# design.net
KiCad netlist of a schematic drawn in Altium Designer
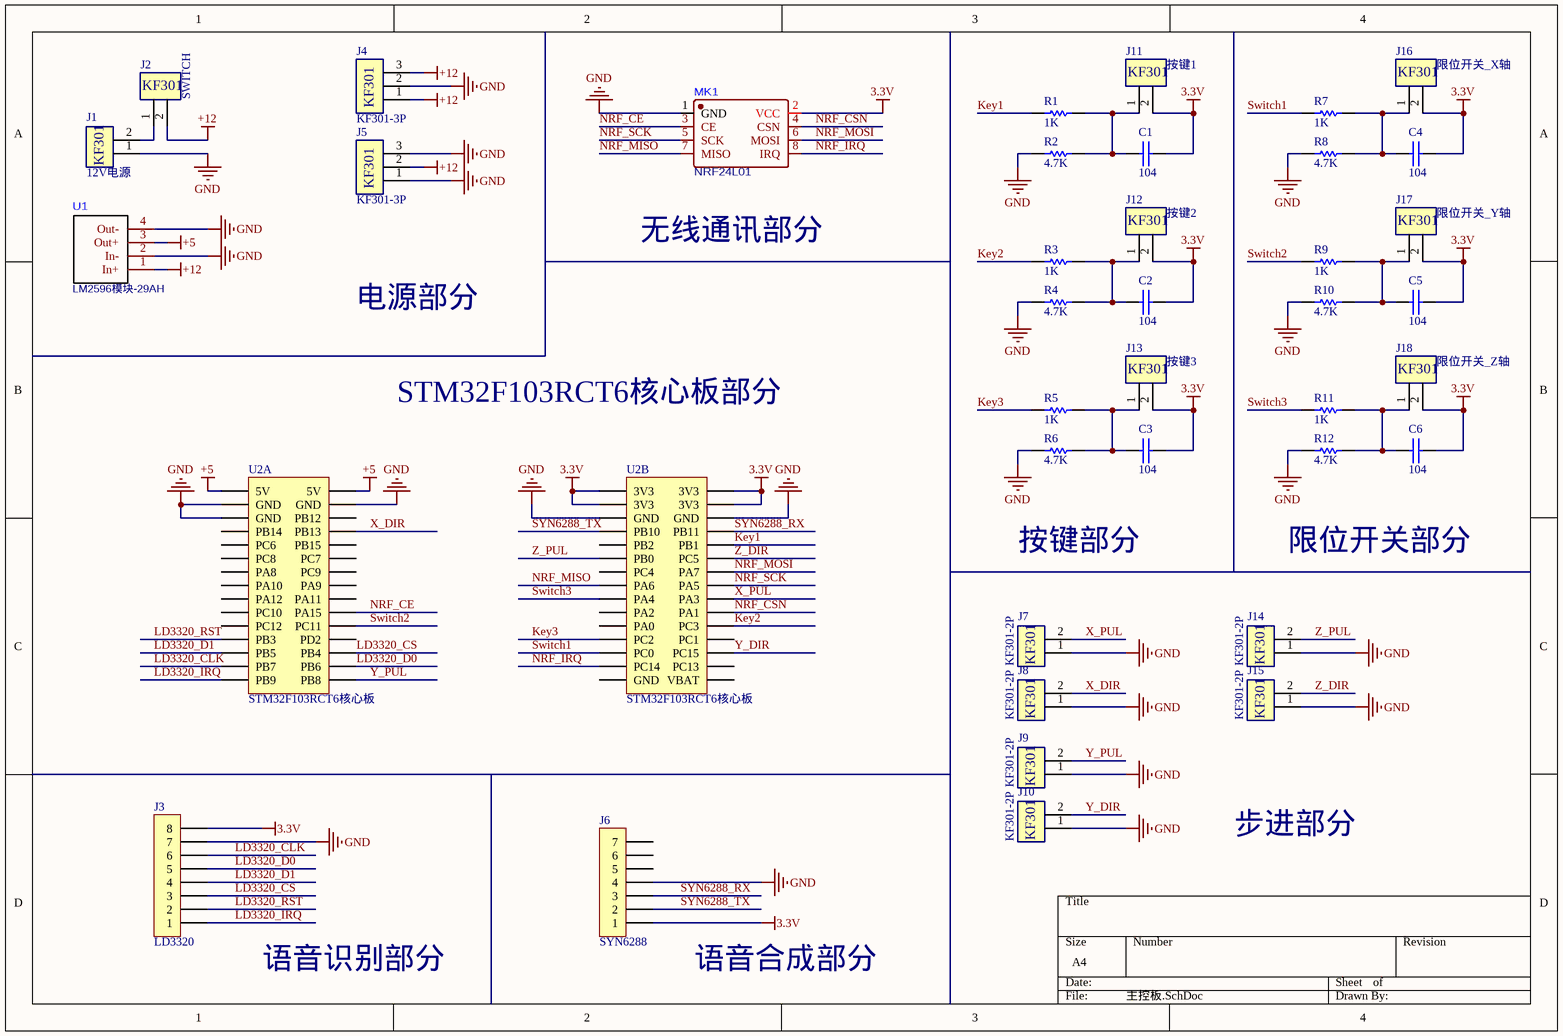
[diagram p0: 主控板.SchDoc]

(export (version "E")
  (design (tool "Eeschema 10.0.6"))
  (components
    (comp (ref "C1")
      (value "104")
      (footprint "0805C")
      (description "无极性电容")
      (libsource (lib "电容") (part "CAP"))
    )
    (comp (ref "C2")
      (value "104")
      (footprint "0805C")
      (description "无极性电容")
      (libsource (lib "电容") (part "CAP"))
    )
    (comp (ref "C3")
      (value "104")
      (footprint "0805C")
      (description "无极性电容")
      (libsource (lib "电容") (part "CAP"))
    )
    (comp (ref "C4")
      (value "104")
      (footprint "0805C")
      (description "无极性电容")
      (libsource (lib "电容") (part "CAP"))
    )
    (comp (ref "C5")
      (value "104")
      (footprint "0805C")
      (description "无极性电容")
      (libsource (lib "电容") (part "CAP"))
    )
    (comp (ref "C6")
      (value "104")
      (footprint "0805C")
      (description "无极性电容")
      (libsource (lib "电容") (part "CAP"))
    )
    (comp (ref "J1") (value "12V电源") (footprint "KF301-5.0-2P") (libsource (lib "") (part "KF301-2P_1")))
    (comp (ref "J2") (value "SWITCH") (footprint "KF301-5.0-2P") (libsource (lib "KF301") (part "KF301-2P")))
    (comp (ref "J3")
      (value "LD3320")
      (footprint "Fe-HDR1X8/2.54-S")
      (libsource (lib "排母") (part "Female HDR1X8"))
    )
    (comp (ref "J4")
      (value "KF301-3P")
      (footprint "KF301-5.0-3P")
      (libsource (lib "KF301") (part "KF301-3P"))
    )
    (comp (ref "J5")
      (value "KF301-3P")
      (footprint "KF301-5.0-3P")
      (libsource (lib "KF301") (part "KF301-3P"))
    )
    (comp (ref "J6")
      (value "SYN6288")
      (footprint "Fe-HDR1X7/2.54-S")
      (libsource (lib "排母") (part "Female HDR1X7"))
    )
    (comp (ref "J7") (value "KF301-2P") (footprint "KF301-5.0-2P") (libsource (lib "") (part "KF301-2P_1")))
    (comp (ref "J8") (value "KF301-2P") (footprint "KF301-5.0-2P") (libsource (lib "") (part "KF301-2P_1")))
    (comp (ref "J9") (value "KF301-2P") (footprint "KF301-5.0-2P") (libsource (lib "") (part "KF301-2P_1")))
    (comp (ref "J10") (value "KF301-2P") (footprint "KF301-5.0-2P") (libsource (lib "") (part "KF301-2P_1")))
    (comp (ref "J11") (value "按键1") (footprint "KF301-5.0-2P") (libsource (lib "KF301") (part "KF301-2P")))
    (comp (ref "J12") (value "按键2") (footprint "KF301-5.0-2P") (libsource (lib "KF301") (part "KF301-2P")))
    (comp (ref "J13") (value "按键3") (footprint "KF301-5.0-2P") (libsource (lib "KF301") (part "KF301-2P")))
    (comp (ref "J14") (value "KF301-2P") (footprint "KF301-5.0-2P") (libsource (lib "") (part "KF301-2P_1")))
    (comp (ref "J15") (value "KF301-2P") (footprint "KF301-5.0-2P") (libsource (lib "") (part "KF301-2P_1")))
    (comp (ref "J16")
      (value "限位开关_X轴")
      (footprint "KF301-5.0-2P")
      (libsource (lib "KF301") (part "KF301-2P"))
    )
    (comp (ref "J17")
      (value "限位开关_Y轴")
      (footprint "KF301-5.0-2P")
      (libsource (lib "KF301") (part "KF301-2P"))
    )
    (comp (ref "J18")
      (value "限位开关_Z轴")
      (footprint "KF301-5.0-2P")
      (libsource (lib "KF301") (part "KF301-2P"))
    )
    (comp (ref "MK1")
      (value "NRF24L01")
      (footprint "WIRELM-SMD_NRF24L01")
      (libsource (lib "zy lib") (part "NRF24L01"))
    )
    (comp (ref "R1") (value "1K") (footprint "0805R") (libsource (lib "电阻") (part "RES")))
    (comp (ref "R2") (value "4.7K") (footprint "0805R") (libsource (lib "电阻") (part "RES")))
    (comp (ref "R3") (value "1K") (footprint "0805R") (libsource (lib "电阻") (part "RES")))
    (comp (ref "R4") (value "4.7K") (footprint "0805R") (libsource (lib "电阻") (part "RES")))
    (comp (ref "R5") (value "1K") (footprint "0805R") (libsource (lib "电阻") (part "RES")))
    (comp (ref "R6") (value "4.7K") (footprint "0805R") (libsource (lib "电阻") (part "RES")))
    (comp (ref "R7") (value "1K") (footprint "0805R") (libsource (lib "电阻") (part "RES")))
    (comp (ref "R8") (value "4.7K") (footprint "0805R") (libsource (lib "电阻") (part "RES")))
    (comp (ref "R9") (value "1K") (footprint "0805R") (libsource (lib "电阻") (part "RES")))
    (comp (ref "R10") (value "4.7K") (footprint "0805R") (libsource (lib "电阻") (part "RES")))
    (comp (ref "R11") (value "1K") (footprint "0805R") (libsource (lib "电阻") (part "RES")))
    (comp (ref "R12") (value "4.7K") (footprint "0805R") (libsource (lib "电阻") (part "RES")))
    (comp (ref "U1")
      (value "LM2596模块-29AH")
      (footprint "LM2596")
      (libsource (lib "zy lib") (part "LM2596模块-29AH"))
    )
    (comp (ref "U2")
      (value "STM32F103RCT6核心板")
      (footprint "STM32F103RC")
      (libsource (lib "zy lib") (part "STM32F103RCT6核心板"))
    )
  )
  (nets
    (net (code "1") (name "+5") (class "Default")
      (node (ref "U1") (pin "3") (pinfunction "Out+_3") (pintype "passive"))
      (node (ref "U2") (pin "1") (pinfunction "5V_1") (pintype "passive"))
      (node (ref "U2") (pin "2") (pinfunction "5V_2") (pintype "passive"))
    )
    (net (code "2") (name "+12") (class "Default")
      (node (ref "J2") (pin "2") (pinfunction "2_2") (pintype "passive"))
      (node (ref "J4") (pin "1") (pinfunction "1_1") (pintype "passive"))
      (node (ref "J4") (pin "3") (pinfunction "3_3") (pintype "passive"))
      (node (ref "J5") (pin "2") (pinfunction "2_2") (pintype "passive"))
      (node (ref "U1") (pin "1") (pinfunction "In+_1") (pintype "passive"))
    )
    (net (code "3") (name "/Key1") (class "Default")
      (node (ref "R1") (pin "1") (pinfunction "1_1") (pintype "passive"))
      (node (ref "U2") (pin "40") (pinfunction "PB1_40") (pintype "passive"))
    )
    (net (code "4") (name "/Key2") (class "Default")
      (node (ref "R3") (pin "1") (pinfunction "1_1") (pintype "passive"))
      (node (ref "U2") (pin "52") (pinfunction "PC3_52") (pintype "passive"))
    )
    (net (code "5") (name "/Key3") (class "Default")
      (node (ref "R5") (pin "1") (pinfunction "1_1") (pintype "passive"))
      (node (ref "U2") (pin "53") (pinfunction "PC2_53") (pintype "passive"))
    )
    (net (code "6") (name "/LD3320_CLK") (class "Default")
      (node (ref "J3") (pin "6") (pinfunction "6_6") (pintype "passive"))
      (node (ref "U2") (pin "27") (pinfunction "PB7_27") (pintype "passive"))
    )
    (net (code "7") (name "/LD3320_CS") (class "Default")
      (node (ref "J3") (pin "3") (pinfunction "3_3") (pintype "passive"))
      (node (ref "U2") (pin "26") (pinfunction "PB4_26") (pintype "passive"))
    )
    (net (code "8") (name "/LD3320_D0") (class "Default")
      (node (ref "J3") (pin "5") (pinfunction "5_5") (pintype "passive"))
      (node (ref "U2") (pin "28") (pinfunction "PB6_28") (pintype "passive"))
    )
    (net (code "9") (name "/LD3320_D1") (class "Default")
      (node (ref "J3") (pin "4") (pinfunction "4_4") (pintype "passive"))
      (node (ref "U2") (pin "25") (pinfunction "PB5_25") (pintype "passive"))
    )
    (net (code "10") (name "/LD3320_IRQ") (class "Default")
      (node (ref "J3") (pin "1") (pinfunction "1_1") (pintype "passive"))
      (node (ref "U2") (pin "29") (pinfunction "PB9_29") (pintype "passive"))
    )
    (net (code "11") (name "/LD3320_RST") (class "Default")
      (node (ref "J3") (pin "2") (pinfunction "2_2") (pintype "passive"))
      (node (ref "U2") (pin "23") (pinfunction "PB3_23") (pintype "passive"))
    )
    (net (code "12") (name "/NRF_CE") (class "Default")
      (node (ref "MK1") (pin "3") (pinfunction "CE_3") (pintype "passive"))
      (node (ref "U2") (pin "20") (pinfunction "PA15_20") (pintype "passive"))
    )
    (net (code "13") (name "/NRF_CSN") (class "Default")
      (node (ref "MK1") (pin "4") (pinfunction "CSN_4") (pintype "passive"))
      (node (ref "U2") (pin "50") (pinfunction "PA1_50") (pintype "passive"))
    )
    (net (code "14") (name "/NRF_IRQ") (class "Default")
      (node (ref "MK1") (pin "8") (pinfunction "IRQ_8") (pintype "passive"))
      (node (ref "U2") (pin "57") (pinfunction "PC14_57") (pintype "passive"))
    )
    (net (code "15") (name "/NRF_MISO") (class "Default")
      (node (ref "MK1") (pin "7") (pinfunction "MISO_7") (pintype "passive"))
      (node (ref "U2") (pin "45") (pinfunction "PA6_45") (pintype "passive"))
    )
    (net (code "16") (name "/NRF_MOSI") (class "Default")
      (node (ref "MK1") (pin "6") (pinfunction "MOSI_6") (pintype "passive"))
      (node (ref "U2") (pin "44") (pinfunction "PA7_44") (pintype "passive"))
    )
    (net (code "17") (name "/NRF_SCK") (class "Default")
      (node (ref "MK1") (pin "5") (pinfunction "SCK_5") (pintype "passive"))
      (node (ref "U2") (pin "46") (pinfunction "PA5_46") (pintype "passive"))
    )
    (net (code "18") (name "/SYN6288_RX") (class "Default")
      (node (ref "J6") (pin "3") (pinfunction "3_3") (pintype "passive"))
      (node (ref "U2") (pin "38") (pinfunction "PB11_38") (pintype "passive"))
    )
    (net (code "19") (name "/SYN6288_TX") (class "Default")
      (node (ref "J6") (pin "2") (pinfunction "2_2") (pintype "passive"))
      (node (ref "U2") (pin "37") (pinfunction "PB10_37") (pintype "passive"))
    )
    (net (code "20") (name "/Switch1") (class "Default")
      (node (ref "R7") (pin "1") (pinfunction "1_1") (pintype "passive"))
      (node (ref "U2") (pin "55") (pinfunction "PC0_55") (pintype "passive"))
    )
    (net (code "21") (name "/Switch2") (class "Default")
      (node (ref "R9") (pin "1") (pinfunction "1_1") (pintype "passive"))
      (node (ref "U2") (pin "22") (pinfunction "PC11_22") (pintype "passive"))
    )
    (net (code "22") (name "/Switch3") (class "Default")
      (node (ref "R11") (pin "1") (pinfunction "1_1") (pintype "passive"))
      (node (ref "U2") (pin "47") (pinfunction "PA4_47") (pintype "passive"))
    )
    (net (code "23") (name "/X_DIR") (class "Default")
      (node (ref "J8") (pin "2") (pinfunction "2_2") (pintype "passive"))
      (node (ref "U2") (pin "8") (pinfunction "PB13_8") (pintype "passive"))
    )
    (net (code "24") (name "/X_PUL") (class "Default")
      (node (ref "J7") (pin "2") (pinfunction "2_2") (pintype "passive"))
      (node (ref "U2") (pin "48") (pinfunction "PA3_48") (pintype "passive"))
    )
    (net (code "25") (name "/Y_DIR") (class "Default")
      (node (ref "J10") (pin "2") (pinfunction "2_2") (pintype "passive"))
      (node (ref "U2") (pin "56") (pinfunction "PC15_56") (pintype "passive"))
    )
    (net (code "26") (name "/Y_PUL") (class "Default")
      (node (ref "J9") (pin "2") (pinfunction "2_2") (pintype "passive"))
      (node (ref "U2") (pin "30") (pinfunction "PB8_30") (pintype "passive"))
    )
    (net (code "27") (name "/Z_DIR") (class "Default")
      (node (ref "J15") (pin "2") (pinfunction "2_2") (pintype "passive"))
      (node (ref "U2") (pin "42") (pinfunction "PC5_42") (pintype "passive"))
    )
    (net (code "28") (name "/Z_PUL") (class "Default")
      (node (ref "J14") (pin "2") (pinfunction "2_2") (pintype "passive"))
      (node (ref "U2") (pin "41") (pinfunction "PB0_41") (pintype "passive"))
    )
    (net (code "29") (name "3.3V") (class "Default")
      (node (ref "C1") (pin "2") (pinfunction "2_2") (pintype "passive"))
      (node (ref "C2") (pin "2") (pinfunction "2_2") (pintype "passive"))
      (node (ref "C3") (pin "2") (pinfunction "2_2") (pintype "passive"))
      (node (ref "C4") (pin "2") (pinfunction "2_2") (pintype "passive"))
      (node (ref "C5") (pin "2") (pinfunction "2_2") (pintype "passive"))
      (node (ref "C6") (pin "2") (pinfunction "2_2") (pintype "passive"))
      (node (ref "J11") (pin "2") (pinfunction "2_2") (pintype "passive"))
      (node (ref "J12") (pin "2") (pinfunction "2_2") (pintype "passive"))
      (node (ref "J13") (pin "2") (pinfunction "2_2") (pintype "passive"))
      (node (ref "J16") (pin "2") (pinfunction "2_2") (pintype "passive"))
      (node (ref "J17") (pin "2") (pinfunction "2_2") (pintype "passive"))
      (node (ref "J18") (pin "2") (pinfunction "2_2") (pintype "passive"))
      (node (ref "J3") (pin "8") (pinfunction "8_8") (pintype "passive"))
      (node (ref "J6") (pin "1") (pinfunction "1_1") (pintype "passive"))
      (node (ref "MK1") (pin "2") (pinfunction "VCC_2") (pintype "passive"))
      (node (ref "U2") (pin "31") (pinfunction "3V3_31") (pintype "passive"))
      (node (ref "U2") (pin "32") (pinfunction "3V3_32") (pintype "passive"))
      (node (ref "U2") (pin "33") (pinfunction "3V3_33") (pintype "passive"))
      (node (ref "U2") (pin "34") (pinfunction "3V3_34") (pintype "passive"))
    )
    (net (code "30") (name "GND") (class "Default")
      (node (ref "J1") (pin "1") (pinfunction "1_1") (pintype "passive"))
      (node (ref "J10") (pin "1") (pinfunction "1_1") (pintype "passive"))
      (node (ref "J14") (pin "1") (pinfunction "1_1") (pintype "passive"))
      (node (ref "J15") (pin "1") (pinfunction "1_1") (pintype "passive"))
      (node (ref "J3") (pin "7") (pinfunction "7_7") (pintype "passive"))
      (node (ref "J4") (pin "2") (pinfunction "2_2") (pintype "passive"))
      (node (ref "J5") (pin "1") (pinfunction "1_1") (pintype "passive"))
      (node (ref "J5") (pin "3") (pinfunction "3_3") (pintype "passive"))
      (node (ref "J6") (pin "4") (pinfunction "4_4") (pintype "passive"))
      (node (ref "J7") (pin "1") (pinfunction "1_1") (pintype "passive"))
      (node (ref "J8") (pin "1") (pinfunction "1_1") (pintype "passive"))
      (node (ref "J9") (pin "1") (pinfunction "1_1") (pintype "passive"))
      (node (ref "MK1") (pin "1") (pinfunction "GND_1") (pintype "passive"))
      (node (ref "R10") (pin "1") (pinfunction "1_1") (pintype "passive"))
      (node (ref "R12") (pin "1") (pinfunction "1_1") (pintype "passive"))
      (node (ref "R2") (pin "1") (pinfunction "1_1") (pintype "passive"))
      (node (ref "R4") (pin "1") (pinfunction "1_1") (pintype "passive"))
      (node (ref "R6") (pin "1") (pinfunction "1_1") (pintype "passive"))
      (node (ref "R8") (pin "1") (pinfunction "1_1") (pintype "passive"))
      (node (ref "U1") (pin "2") (pinfunction "In-_2") (pintype "passive"))
      (node (ref "U1") (pin "4") (pinfunction "Out-_4") (pintype "passive"))
      (node (ref "U2") (pin "3") (pinfunction "GND_3") (pintype "passive"))
      (node (ref "U2") (pin "35") (pinfunction "GND_35") (pintype "passive"))
      (node (ref "U2") (pin "36") (pinfunction "GND_36") (pintype "passive"))
      (node (ref "U2") (pin "4") (pinfunction "GND_4") (pintype "passive"))
      (node (ref "U2") (pin "5") (pinfunction "GND_5") (pintype "passive"))
    )
    (net (code "31") (name "Net-(C1-Pad1)") (class "Default")
      (node (ref "C1") (pin "1") (pinfunction "1_1") (pintype "passive"))
      (node (ref "J11") (pin "1") (pinfunction "1_1") (pintype "passive"))
      (node (ref "R1") (pin "2") (pinfunction "2_2") (pintype "passive"))
      (node (ref "R2") (pin "2") (pinfunction "2_2") (pintype "passive"))
    )
    (net (code "32") (name "Net-(C2-Pad1)") (class "Default")
      (node (ref "C2") (pin "1") (pinfunction "1_1") (pintype "passive"))
      (node (ref "J12") (pin "1") (pinfunction "1_1") (pintype "passive"))
      (node (ref "R3") (pin "2") (pinfunction "2_2") (pintype "passive"))
      (node (ref "R4") (pin "2") (pinfunction "2_2") (pintype "passive"))
    )
    (net (code "33") (name "Net-(C3-Pad1)") (class "Default")
      (node (ref "C3") (pin "1") (pinfunction "1_1") (pintype "passive"))
      (node (ref "J13") (pin "1") (pinfunction "1_1") (pintype "passive"))
      (node (ref "R5") (pin "2") (pinfunction "2_2") (pintype "passive"))
      (node (ref "R6") (pin "2") (pinfunction "2_2") (pintype "passive"))
    )
    (net (code "34") (name "Net-(C4-Pad1)") (class "Default")
      (node (ref "C4") (pin "1") (pinfunction "1_1") (pintype "passive"))
      (node (ref "J16") (pin "1") (pinfunction "1_1") (pintype "passive"))
      (node (ref "R7") (pin "2") (pinfunction "2_2") (pintype "passive"))
      (node (ref "R8") (pin "2") (pinfunction "2_2") (pintype "passive"))
    )
    (net (code "35") (name "Net-(C5-Pad1)") (class "Default")
      (node (ref "C5") (pin "1") (pinfunction "1_1") (pintype "passive"))
      (node (ref "J17") (pin "1") (pinfunction "1_1") (pintype "passive"))
      (node (ref "R10") (pin "2") (pinfunction "2_2") (pintype "passive"))
      (node (ref "R9") (pin "2") (pinfunction "2_2") (pintype "passive"))
    )
    (net (code "36") (name "Net-(C6-Pad1)") (class "Default")
      (node (ref "C6") (pin "1") (pinfunction "1_1") (pintype "passive"))
      (node (ref "J18") (pin "1") (pinfunction "1_1") (pintype "passive"))
      (node (ref "R11") (pin "2") (pinfunction "2_2") (pintype "passive"))
      (node (ref "R12") (pin "2") (pinfunction "2_2") (pintype "passive"))
    )
    (net (code "37") (name "Net-(J1-Pad2)") (class "Default")
      (node (ref "J1") (pin "2") (pinfunction "2_2") (pintype "passive"))
      (node (ref "J2") (pin "1") (pinfunction "1_1") (pintype "passive"))
    )
    (net (code "38") (name "unconnected-(J6-Pad5)") (class "Default")
      (node (ref "J6") (pin "5") (pinfunction "5_5") (pintype "passive"))
    )
    (net (code "39") (name "unconnected-(J6-Pad6)") (class "Default")
      (node (ref "J6") (pin "6") (pinfunction "6_6") (pintype "passive"))
    )
    (net (code "40") (name "unconnected-(J6-Pad7)") (class "Default")
      (node (ref "J6") (pin "7") (pinfunction "7_7") (pintype "passive"))
    )
    (net (code "41") (name "unconnected-(U2A-PA8-Pad13)") (class "Default")
      (node (ref "U2") (pin "13") (pinfunction "PA8_13") (pintype "passive"))
    )
    (net (code "42") (name "unconnected-(U2A-PA9-Pad16)") (class "Default")
      (node (ref "U2") (pin "16") (pinfunction "PA9_16") (pintype "passive"))
    )
    (net (code "43") (name "unconnected-(U2A-PA10-Pad15)") (class "Default")
      (node (ref "U2") (pin "15") (pinfunction "PA10_15") (pintype "passive"))
    )
    (net (code "44") (name "unconnected-(U2A-PA11-Pad18)") (class "Default")
      (node (ref "U2") (pin "18") (pinfunction "PA11_18") (pintype "passive"))
    )
    (net (code "45") (name "unconnected-(U2A-PA12-Pad17)") (class "Default")
      (node (ref "U2") (pin "17") (pinfunction "PA12_17") (pintype "passive"))
    )
    (net (code "46") (name "unconnected-(U2A-PB12-Pad6)") (class "Default")
      (node (ref "U2") (pin "6") (pinfunction "PB12_6") (pintype "passive"))
    )
    (net (code "47") (name "unconnected-(U2A-PB14-Pad7)") (class "Default")
      (node (ref "U2") (pin "7") (pinfunction "PB14_7") (pintype "passive"))
    )
    (net (code "48") (name "unconnected-(U2A-PB15-Pad10)") (class "Default")
      (node (ref "U2") (pin "10") (pinfunction "PB15_10") (pintype "passive"))
    )
    (net (code "49") (name "unconnected-(U2A-PC6-Pad9)") (class "Default")
      (node (ref "U2") (pin "9") (pinfunction "PC6_9") (pintype "passive"))
    )
    (net (code "50") (name "unconnected-(U2A-PC7-Pad12)") (class "Default")
      (node (ref "U2") (pin "12") (pinfunction "PC7_12") (pintype "passive"))
    )
    (net (code "51") (name "unconnected-(U2A-PC8-Pad11)") (class "Default")
      (node (ref "U2") (pin "11") (pinfunction "PC8_11") (pintype "passive"))
    )
    (net (code "52") (name "unconnected-(U2A-PC9-Pad14)") (class "Default")
      (node (ref "U2") (pin "14") (pinfunction "PC9_14") (pintype "passive"))
    )
    (net (code "53") (name "unconnected-(U2A-PC10-Pad19)") (class "Default")
      (node (ref "U2") (pin "19") (pinfunction "PC10_19") (pintype "passive"))
    )
    (net (code "54") (name "unconnected-(U2A-PC12-Pad21)") (class "Default")
      (node (ref "U2") (pin "21") (pinfunction "PC12_21") (pintype "passive"))
    )
    (net (code "55") (name "unconnected-(U2A-PD2-Pad24)") (class "Default")
      (node (ref "U2") (pin "24") (pinfunction "PD2_24") (pintype "passive"))
    )
    (net (code "56") (name "unconnected-(U2B-GND-Pad59)") (class "Default")
      (node (ref "U2") (pin "59") (pinfunction "GND_59") (pintype "passive"))
    )
    (net (code "57") (name "unconnected-(U2B-PA0-Pad51)") (class "Default")
      (node (ref "U2") (pin "51") (pinfunction "PA0_51") (pintype "passive"))
    )
    (net (code "58") (name "unconnected-(U2B-PA2-Pad49)") (class "Default")
      (node (ref "U2") (pin "49") (pinfunction "PA2_49") (pintype "passive"))
    )
    (net (code "59") (name "unconnected-(U2B-PB2-Pad39)") (class "Default")
      (node (ref "U2") (pin "39") (pinfunction "PB2_39") (pintype "passive"))
    )
    (net (code "60") (name "unconnected-(U2B-PC1-Pad54)") (class "Default")
      (node (ref "U2") (pin "54") (pinfunction "PC1_54") (pintype "passive"))
    )
    (net (code "61") (name "unconnected-(U2B-PC4-Pad43)") (class "Default")
      (node (ref "U2") (pin "43") (pinfunction "PC4_43") (pintype "passive"))
    )
    (net (code "62") (name "unconnected-(U2B-PC13-Pad58)") (class "Default")
      (node (ref "U2") (pin "58") (pinfunction "PC13_58") (pintype "passive"))
    )
    (net (code "63") (name "unconnected-(U2B-VBAT-Pad60)") (class "Default")
      (node (ref "U2") (pin "60") (pinfunction "VBAT_60") (pintype "passive"))
    )
  )
)
